# Main.net
KiCad netlist of a schematic drawn in Altium Designer
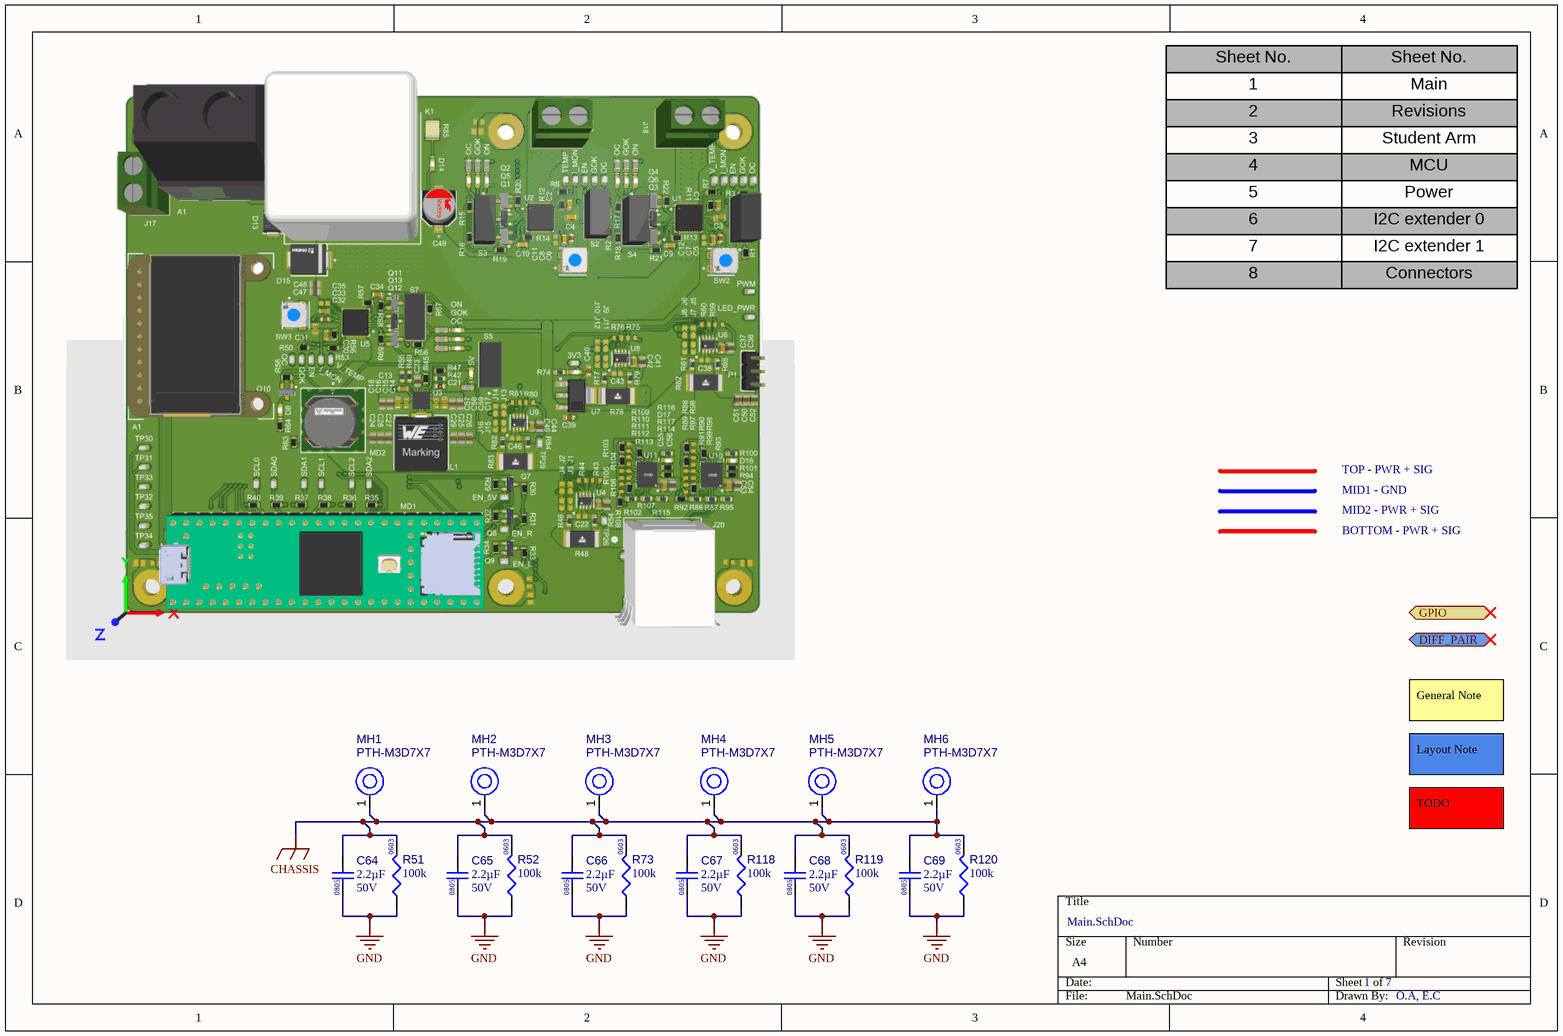
[diagram p0: Main.SchDoc]

(export (version "E")
  (design (tool "Eeschema 10.0.6"))
  (components
    (comp (ref "C64")
      (value "2.2µF")
      (footprint "FP-CL21-IPC_C")
      (fields
        (field (name "RATED DC VOLTAGE (URDC)") "50V")
        (field (name "CASE/PACKAGE") "0805")
        (field (name "Comment") "CL21A225KBFNNNE")
      )
      (libsource (lib "hawaiirobotics") (part "CAP-NP-2"))
    )
    (comp (ref "C65")
      (value "2.2µF")
      (footprint "FP-CL21-IPC_C")
      (fields
        (field (name "RATED DC VOLTAGE (URDC)") "50V")
        (field (name "CASE/PACKAGE") "0805")
        (field (name "Comment") "CL21A225KBFNNNE")
      )
      (libsource (lib "hawaiirobotics") (part "CAP-NP-2"))
    )
    (comp (ref "C66")
      (value "2.2µF")
      (footprint "FP-CL21-IPC_C")
      (fields
        (field (name "RATED DC VOLTAGE (URDC)") "50V")
        (field (name "CASE/PACKAGE") "0805")
        (field (name "Comment") "CL21A225KBFNNNE")
      )
      (libsource (lib "hawaiirobotics") (part "CAP-NP-2"))
    )
    (comp (ref "C67")
      (value "2.2µF")
      (footprint "FP-CL21-IPC_C")
      (fields
        (field (name "RATED DC VOLTAGE (URDC)") "50V")
        (field (name "CASE/PACKAGE") "0805")
        (field (name "Comment") "CL21A225KBFNNNE")
      )
      (libsource (lib "hawaiirobotics") (part "CAP-NP-2"))
    )
    (comp (ref "C68")
      (value "2.2µF")
      (footprint "FP-CL21-IPC_C")
      (fields
        (field (name "RATED DC VOLTAGE (URDC)") "50V")
        (field (name "CASE/PACKAGE") "0805")
        (field (name "Comment") "CL21A225KBFNNNE")
      )
      (libsource (lib "hawaiirobotics") (part "CAP-NP-2"))
    )
    (comp (ref "C69")
      (value "2.2µF")
      (footprint "FP-CL21-IPC_C")
      (fields
        (field (name "RATED DC VOLTAGE (URDC)") "50V")
        (field (name "CASE/PACKAGE") "0805")
        (field (name "Comment") "CL21A225KBFNNNE")
      )
      (libsource (lib "hawaiirobotics") (part "CAP-NP-2"))
    )
    (comp (ref "MH1")
      (value "PTH-M3D7X7")
      (footprint "PTH-M2D5X5")
      (description "M3 PTH (3.3mm), 7mm pad")
      (libsource (lib "hawaiirobotics") (part "CMP-00028-00000-1"))
    )
    (comp (ref "MH2")
      (value "PTH-M3D7X7")
      (footprint "PTH-M2D5X5")
      (description "M3 PTH (3.3mm), 7mm pad")
      (libsource (lib "hawaiirobotics") (part "CMP-00028-00000-1"))
    )
    (comp (ref "MH3")
      (value "PTH-M3D7X7")
      (footprint "PTH-M2D5X5")
      (description "M3 PTH (3.3mm), 7mm pad")
      (libsource (lib "hawaiirobotics") (part "CMP-00028-00000-1"))
    )
    (comp (ref "MH4")
      (value "PTH-M3D7X7")
      (footprint "PTH-M2D5X5")
      (description "M3 PTH (3.3mm), 7mm pad")
      (libsource (lib "hawaiirobotics") (part "CMP-00028-00000-1"))
    )
    (comp (ref "MH5")
      (value "PTH-M3D7X7")
      (footprint "PTH-M2D5X5")
      (description "M3 PTH (3.3mm), 7mm pad")
      (libsource (lib "hawaiirobotics") (part "CMP-00028-00000-1"))
    )
    (comp (ref "MH6")
      (value "PTH-M3D7X7")
      (footprint "PTH-M2D5X5")
      (description "M3 PTH (3.3mm), 7mm pad")
      (libsource (lib "hawaiirobotics") (part "CMP-00028-00000-1"))
    )
    (comp (ref "R51")
      (value "100k")
      (footprint "RESC1608X55X25NL10T15")
      (fields
        (field (name "POWER") "100mW")
        (field (name "TOLERANCE") "1%")
        (field (name "CASE/PACKAGE") "0603")
        (field (name "Comment") "RC0603FR-07100KL")
      )
      (libsource (lib "hawaiirobotics") (part "RES-2"))
    )
    (comp (ref "R52")
      (value "100k")
      (footprint "RESC1608X55X25NL10T15")
      (fields
        (field (name "POWER") "100mW")
        (field (name "TOLERANCE") "1%")
        (field (name "CASE/PACKAGE") "0603")
        (field (name "Comment") "RC0603FR-07100KL")
      )
      (libsource (lib "hawaiirobotics") (part "RES-2"))
    )
    (comp (ref "R73")
      (value "100k")
      (footprint "RESC1608X55X25NL10T15")
      (fields
        (field (name "POWER") "100mW")
        (field (name "TOLERANCE") "1%")
        (field (name "CASE/PACKAGE") "0603")
        (field (name "Comment") "RC0603FR-07100KL")
      )
      (libsource (lib "hawaiirobotics") (part "RES-2"))
    )
    (comp (ref "R118")
      (value "100k")
      (footprint "RESC1608X55X25NL10T15")
      (fields
        (field (name "POWER") "100mW")
        (field (name "TOLERANCE") "1%")
        (field (name "CASE/PACKAGE") "0603")
        (field (name "Comment") "RC0603FR-07100KL")
      )
      (libsource (lib "hawaiirobotics") (part "RES-2"))
    )
    (comp (ref "R119")
      (value "100k")
      (footprint "RESC1608X55X25NL10T15")
      (fields
        (field (name "POWER") "100mW")
        (field (name "TOLERANCE") "1%")
        (field (name "CASE/PACKAGE") "0603")
        (field (name "Comment") "RC0603FR-07100KL")
      )
      (libsource (lib "hawaiirobotics") (part "RES-2"))
    )
    (comp (ref "R120")
      (value "100k")
      (footprint "RESC1608X55X25NL10T15")
      (fields
        (field (name "POWER") "100mW")
        (field (name "TOLERANCE") "1%")
        (field (name "CASE/PACKAGE") "0603")
        (field (name "Comment") "RC0603FR-07100KL")
      )
      (libsource (lib "hawaiirobotics") (part "RES-2"))
    )
  )
  (nets
    (net (code "3") (name "CHASSIS") (class "Default")
      (node (ref "C64") (pin "2") (pinfunction "2_2") (pintype "passive"))
      (node (ref "C65") (pin "2") (pinfunction "2_2") (pintype "passive"))
      (node (ref "C66") (pin "2") (pinfunction "2_2") (pintype "passive"))
      (node (ref "C67") (pin "2") (pinfunction "2_2") (pintype "passive"))
      (node (ref "C68") (pin "2") (pinfunction "2_2") (pintype "passive"))
      (node (ref "C69") (pin "2") (pinfunction "2_2") (pintype "passive"))
      (node (ref "MH1") (pin "1") (pinfunction "H1_1") (pintype "passive"))
      (node (ref "MH2") (pin "1") (pinfunction "H1_1") (pintype "passive"))
      (node (ref "MH3") (pin "1") (pinfunction "H1_1") (pintype "passive"))
      (node (ref "MH4") (pin "1") (pinfunction "H1_1") (pintype "passive"))
      (node (ref "MH5") (pin "1") (pinfunction "H1_1") (pintype "passive"))
      (node (ref "MH6") (pin "1") (pinfunction "H1_1") (pintype "passive"))
      (node (ref "R118") (pin "2") (pinfunction "2_2") (pintype "passive"))
      (node (ref "R119") (pin "2") (pinfunction "2_2") (pintype "passive"))
      (node (ref "R120") (pin "2") (pinfunction "2_2") (pintype "passive"))
      (node (ref "R51") (pin "2") (pinfunction "2_2") (pintype "passive"))
      (node (ref "R52") (pin "2") (pinfunction "2_2") (pintype "passive"))
      (node (ref "R73") (pin "2") (pinfunction "2_2") (pintype "passive"))
    )
    (net (code "4") (name "GND") (class "Default")
      (node (ref "C64") (pin "1") (pinfunction "1_1") (pintype "passive"))
      (node (ref "C65") (pin "1") (pinfunction "1_1") (pintype "passive"))
      (node (ref "C66") (pin "1") (pinfunction "1_1") (pintype "passive"))
      (node (ref "C67") (pin "1") (pinfunction "1_1") (pintype "passive"))
      (node (ref "C68") (pin "1") (pinfunction "1_1") (pintype "passive"))
      (node (ref "C69") (pin "1") (pinfunction "1_1") (pintype "passive"))
      (node (ref "R118") (pin "1") (pinfunction "1_1") (pintype "passive"))
      (node (ref "R119") (pin "1") (pinfunction "1_1") (pintype "passive"))
      (node (ref "R120") (pin "1") (pinfunction "1_1") (pintype "passive"))
      (node (ref "R51") (pin "1") (pinfunction "1_1") (pintype "passive"))
      (node (ref "R52") (pin "1") (pinfunction "1_1") (pintype "passive"))
      (node (ref "R73") (pin "1") (pinfunction "1_1") (pintype "passive"))
    )
  )
)
